# simple-bug-2n918.net
KiCad netlist of a schematic drawn in EAGLE
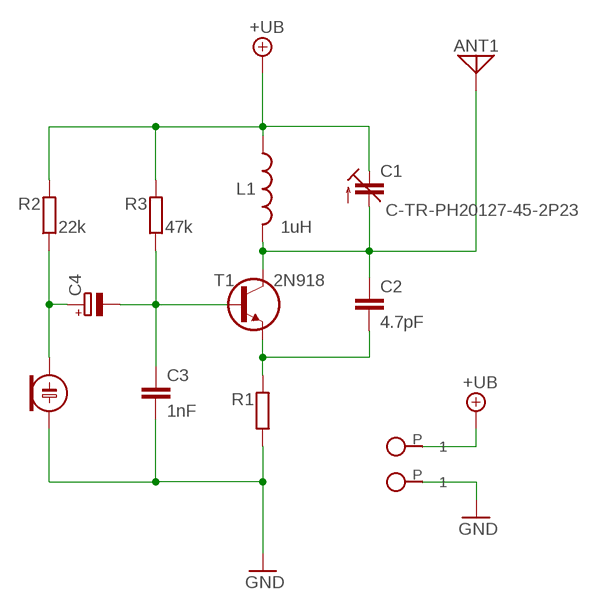
[diagram p0: schematic, sheet 1]

(export (version "E")
  (design (tool "Eeschema 10.0.6"))
  (components
    (comp (ref "+")
      (value "SPAD")
      (footprint "eagle-import:SPAD")
      (libsource (lib "eagle-import") (part "SPAD"))
    )
    (comp (ref "ANT1")
      (value "ANT")
      (footprint "eagle-import:SPAD")
      (libsource (lib "eagle-import") (part "ANT"))
    )
    (comp (ref "C1")
      (value "C-TR-PH20127-45-2P23")
      (footprint "eagle-import:TRIM808-45")
      (libsource (lib "eagle-import") (part "C-TR-PH20127-45-2P23"))
    )
    (comp (ref "C2")
      (value "4.7pF")
      (footprint "eagle-import:C025-020X036")
      (libsource (lib "eagle-import") (part "C025-020X036"))
    )
    (comp (ref "C3")
      (value "1nF")
      (footprint "eagle-import:C025-020X036")
      (libsource (lib "eagle-import") (part "C025-020X036"))
    )
    (comp (ref "C4")
      (value "CPOLE2,5-3")
      (footprint "eagle-import:E2,5-3")
      (libsource (lib "eagle-import") (part "CPOLE2,5-3"))
    )
    (comp (ref "ECM")
      (value "ECM-5")
      (footprint "eagle-import:ECM-5")
      (libsource (lib "eagle-import") (part "ECM-5"))
    )
    (comp (ref "L1")
      (value "1uH")
      (footprint "eagle-import:L-04_7")
      (libsource (lib "eagle-import") (part "L04/7"))
    )
    (comp (ref "R1")
      (value "R0202V")
      (footprint "eagle-import:0202V")
      (libsource (lib "eagle-import") (part "R0202V"))
    )
    (comp (ref "R2")
      (value "22k")
      (footprint "eagle-import:0202_5")
      (libsource (lib "eagle-import") (part "R0202/5"))
    )
    (comp (ref "R3")
      (value "47k")
      (footprint "eagle-import:0202_5")
      (libsource (lib "eagle-import") (part "R0202/5"))
    )
    (comp (ref "T1")
      (value "2N918")
      (footprint "eagle-import:TO-72-A45")
      (libsource (lib "eagle-import") (part "2N918TO-72-A45"))
    )
    (comp (ref "̶̶")
      (value "SPAD")
      (footprint "eagle-import:SPAD")
      (libsource (lib "eagle-import") (part "SPAD"))
    )
  )
  (nets
    (net (code "1") (name "+UB") (class "Default")
      (node (ref "+") (pin "P") (pinfunction "1_P") (pintype "bidirectional"))
      (node (ref "C1") (pin "3") (pinfunction "E_3") (pintype "passive"))
      (node (ref "L1") (pin "1") (pinfunction "1_1") (pintype "passive"))
      (node (ref "R2") (pin "2") (pinfunction "2_2") (pintype "passive"))
      (node (ref "R3") (pin "2") (pinfunction "2_2") (pintype "passive"))
    )
    (net (code "2") (name "GND") (class "Default")
      (node (ref "C3") (pin "2") (pinfunction "2_2") (pintype "passive"))
      (node (ref "ECM") (pin "1") (pinfunction "+_1") (pintype "passive"))
      (node (ref "R1") (pin "1") (pinfunction "1_1") (pintype "passive"))
      (node (ref "̶̶") (pin "P") (pinfunction "1_P") (pintype "bidirectional"))
    )
    (net (code "3") (name "Net-(ANT1-1)") (class "Default")
      (node (ref "ANT1") (pin "P") (pinfunction "1_P") (pintype "output"))
      (node (ref "C1") (pin "2") (pinfunction "A_2") (pintype "passive"))
      (node (ref "C2") (pin "1") (pinfunction "1_1") (pintype "passive"))
      (node (ref "L1") (pin "2") (pinfunction "2_2") (pintype "passive"))
      (node (ref "T1") (pin "3") (pinfunction "C_3") (pintype "passive"))
    )
    (net (code "4") (name "Net-(ECM--)") (class "Default")
      (node (ref "C4") (pin "+") (pinfunction "+_+") (pintype "passive"))
      (node (ref "ECM") (pin "2") (pinfunction "-_2") (pintype "passive"))
      (node (ref "R2") (pin "1") (pinfunction "1_1") (pintype "passive"))
    )
    (net (code "5") (name "Net-(T1-B)") (class "Default")
      (node (ref "C3") (pin "1") (pinfunction "1_1") (pintype "passive"))
      (node (ref "C4") (pin "-") (pinfunction "-_-") (pintype "passive"))
      (node (ref "R3") (pin "1") (pinfunction "1_1") (pintype "passive"))
      (node (ref "T1") (pin "2") (pinfunction "B_2") (pintype "passive"))
    )
    (net (code "6") (name "Net-(T1-E)") (class "Default")
      (node (ref "C2") (pin "2") (pinfunction "2_2") (pintype "passive"))
      (node (ref "R1") (pin "2") (pinfunction "2_2") (pintype "passive"))
      (node (ref "T1") (pin "1") (pinfunction "E_1") (pintype "passive"))
    )
  )
)
